# EasyEDAProPrj_Hackpad_numeric_keypad.net
KiCad netlist of a schematic drawn in EasyEDA Pro
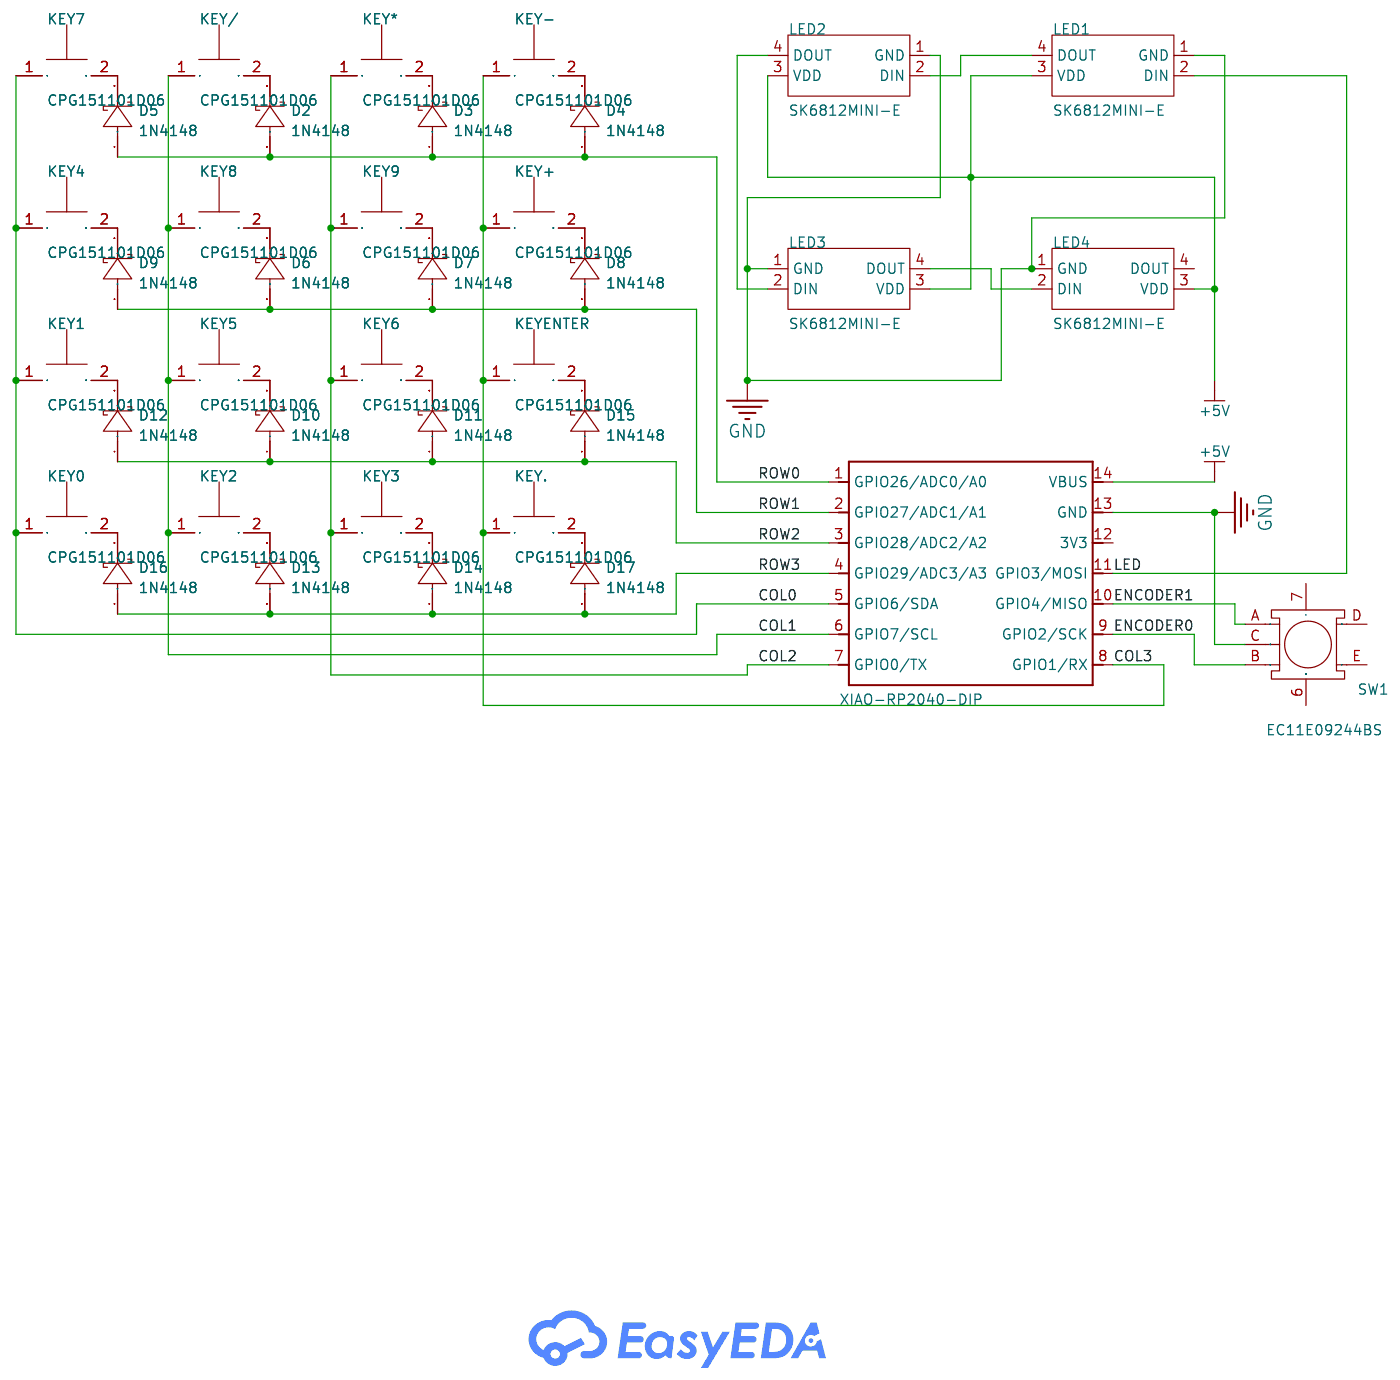
[diagram p0: schematic sheet]

(export (version "E")
  (design (tool "Eeschema 10.0.6"))
  (components
    (comp (ref "D2")
      (value "1N4148")
      (footprint "easyedapro:SOD-123_L2.7-W1.6-LS3.7-FD")
      (fields (field (name "Manufacturer") "LJ(朗捷)"))
      (libsource (lib "easyedapro") (part "1N4148W_C7420318"))
    )
    (comp (ref "D3")
      (value "1N4148")
      (footprint "easyedapro:SOD-123_L2.7-W1.6-LS3.7-FD")
      (fields (field (name "Manufacturer") "LJ(朗捷)"))
      (libsource (lib "easyedapro") (part "1N4148W_C7420318"))
    )
    (comp (ref "D4")
      (value "1N4148")
      (footprint "easyedapro:SOD-123_L2.7-W1.6-LS3.7-FD")
      (fields (field (name "Manufacturer") "LJ(朗捷)"))
      (libsource (lib "easyedapro") (part "1N4148W_C7420318"))
    )
    (comp (ref "D5")
      (value "1N4148")
      (footprint "easyedapro:SOD-123_L2.7-W1.6-LS3.7-FD")
      (fields (field (name "Manufacturer") "LJ(朗捷)"))
      (libsource (lib "easyedapro") (part "1N4148W_C7420318"))
    )
    (comp (ref "D6")
      (value "1N4148")
      (footprint "easyedapro:SOD-123_L2.7-W1.6-LS3.7-FD")
      (fields (field (name "Manufacturer") "LJ(朗捷)"))
      (libsource (lib "easyedapro") (part "1N4148W_C7420318"))
    )
    (comp (ref "D7")
      (value "1N4148")
      (footprint "easyedapro:SOD-123_L2.7-W1.6-LS3.7-FD")
      (fields (field (name "Manufacturer") "LJ(朗捷)"))
      (libsource (lib "easyedapro") (part "1N4148W_C7420318"))
    )
    (comp (ref "D8")
      (value "1N4148")
      (footprint "easyedapro:SOD-123_L2.7-W1.6-LS3.7-FD")
      (fields (field (name "Manufacturer") "LJ(朗捷)"))
      (libsource (lib "easyedapro") (part "1N4148W_C7420318"))
    )
    (comp (ref "D9")
      (value "1N4148")
      (footprint "easyedapro:SOD-123_L2.7-W1.6-LS3.7-FD")
      (fields (field (name "Manufacturer") "LJ(朗捷)"))
      (libsource (lib "easyedapro") (part "1N4148W_C7420318"))
    )
    (comp (ref "D10")
      (value "1N4148")
      (footprint "easyedapro:SOD-123_L2.7-W1.6-LS3.7-FD")
      (fields (field (name "Manufacturer") "LJ(朗捷)"))
      (libsource (lib "easyedapro") (part "1N4148W_C7420318"))
    )
    (comp (ref "D11")
      (value "1N4148")
      (footprint "easyedapro:SOD-123_L2.7-W1.6-LS3.7-FD")
      (fields (field (name "Manufacturer") "LJ(朗捷)"))
      (libsource (lib "easyedapro") (part "1N4148W_C7420318"))
    )
    (comp (ref "D12")
      (value "1N4148")
      (footprint "easyedapro:SOD-123_L2.7-W1.6-LS3.7-FD")
      (fields (field (name "Manufacturer") "LJ(朗捷)"))
      (libsource (lib "easyedapro") (part "1N4148W_C7420318"))
    )
    (comp (ref "D13")
      (value "1N4148")
      (footprint "easyedapro:SOD-123_L2.7-W1.6-LS3.7-FD")
      (fields (field (name "Manufacturer") "LJ(朗捷)"))
      (libsource (lib "easyedapro") (part "1N4148W_C7420318"))
    )
    (comp (ref "D14")
      (value "1N4148")
      (footprint "easyedapro:SOD-123_L2.7-W1.6-LS3.7-FD")
      (fields (field (name "Manufacturer") "LJ(朗捷)"))
      (libsource (lib "easyedapro") (part "1N4148W_C7420318"))
    )
    (comp (ref "D15")
      (value "1N4148")
      (footprint "easyedapro:SOD-123_L2.7-W1.6-LS3.7-FD")
      (fields (field (name "Manufacturer") "LJ(朗捷)"))
      (libsource (lib "easyedapro") (part "1N4148W_C7420318"))
    )
    (comp (ref "D16")
      (value "1N4148")
      (footprint "easyedapro:SOD-123_L2.7-W1.6-LS3.7-FD")
      (fields (field (name "Manufacturer") "LJ(朗捷)"))
      (libsource (lib "easyedapro") (part "1N4148W_C7420318"))
    )
    (comp (ref "D17")
      (value "1N4148")
      (footprint "easyedapro:SOD-123_L2.7-W1.6-LS3.7-FD")
      (fields (field (name "Manufacturer") "LJ(朗捷)"))
      (libsource (lib "easyedapro") (part "1N4148W_C7420318"))
    )
    (comp (ref "KEY*")
      (value "CPG151101D06")
      (footprint "easyedapro:KEY-TH_CPG151101D06")
      (fields (field (name "Manufacturer") "HanElectricity(瀚源)"))
      (libsource (lib "easyedapro") (part "CPG151101D06"))
    )
    (comp (ref "KEY+")
      (value "CPG151101D06")
      (footprint "easyedapro:KEY-TH_CPG151101D06")
      (fields (field (name "Manufacturer") "HanElectricity(瀚源)"))
      (libsource (lib "easyedapro") (part "CPG151101D06"))
    )
    (comp (ref "KEY-")
      (value "CPG151101D06")
      (footprint "easyedapro:KEY-TH_CPG151101D06")
      (fields (field (name "Manufacturer") "HanElectricity(瀚源)"))
      (libsource (lib "easyedapro") (part "CPG151101D06"))
    )
    (comp (ref "KEY.")
      (value "CPG151101D06")
      (footprint "easyedapro:KEY-TH_CPG151101D06")
      (fields (field (name "Manufacturer") "HanElectricity(瀚源)"))
      (libsource (lib "easyedapro") (part "CPG151101D06"))
    )
    (comp (ref "KEY/")
      (value "CPG151101D06")
      (footprint "easyedapro:KEY-TH_CPG151101D06")
      (fields (field (name "Manufacturer") "HanElectricity(瀚源)"))
      (libsource (lib "easyedapro") (part "CPG151101D06"))
    )
    (comp (ref "KEY0")
      (value "CPG151101D06")
      (footprint "easyedapro:KEY-TH_CPG151101D06")
      (fields (field (name "Manufacturer") "HanElectricity(瀚源)"))
      (libsource (lib "easyedapro") (part "CPG151101D06"))
    )
    (comp (ref "KEY1")
      (value "CPG151101D06")
      (footprint "easyedapro:KEY-TH_CPG151101D06")
      (fields (field (name "Manufacturer") "HanElectricity(瀚源)"))
      (libsource (lib "easyedapro") (part "CPG151101D06"))
    )
    (comp (ref "KEY2")
      (value "CPG151101D06")
      (footprint "easyedapro:KEY-TH_CPG151101D06")
      (fields (field (name "Manufacturer") "HanElectricity(瀚源)"))
      (libsource (lib "easyedapro") (part "CPG151101D06"))
    )
    (comp (ref "KEY3")
      (value "CPG151101D06")
      (footprint "easyedapro:KEY-TH_CPG151101D06")
      (fields (field (name "Manufacturer") "HanElectricity(瀚源)"))
      (libsource (lib "easyedapro") (part "CPG151101D06"))
    )
    (comp (ref "KEY4")
      (value "CPG151101D06")
      (footprint "easyedapro:KEY-TH_CPG151101D06")
      (fields (field (name "Manufacturer") "HanElectricity(瀚源)"))
      (libsource (lib "easyedapro") (part "CPG151101D06"))
    )
    (comp (ref "KEY5")
      (value "CPG151101D06")
      (footprint "easyedapro:KEY-TH_CPG151101D06")
      (fields (field (name "Manufacturer") "HanElectricity(瀚源)"))
      (libsource (lib "easyedapro") (part "CPG151101D06"))
    )
    (comp (ref "KEY6")
      (value "CPG151101D06")
      (footprint "easyedapro:KEY-TH_CPG151101D06")
      (fields (field (name "Manufacturer") "HanElectricity(瀚源)"))
      (libsource (lib "easyedapro") (part "CPG151101D06"))
    )
    (comp (ref "KEY7")
      (value "CPG151101D06")
      (footprint "easyedapro:KEY-TH_CPG151101D06")
      (fields (field (name "Manufacturer") "HanElectricity(瀚源)"))
      (libsource (lib "easyedapro") (part "CPG151101D06"))
    )
    (comp (ref "KEY8")
      (value "CPG151101D06")
      (footprint "easyedapro:KEY-TH_CPG151101D06")
      (fields (field (name "Manufacturer") "HanElectricity(瀚源)"))
      (libsource (lib "easyedapro") (part "CPG151101D06"))
    )
    (comp (ref "KEY9")
      (value "CPG151101D06")
      (footprint "easyedapro:KEY-TH_CPG151101D06")
      (fields (field (name "Manufacturer") "HanElectricity(瀚源)"))
      (libsource (lib "easyedapro") (part "CPG151101D06"))
    )
    (comp (ref "KEYENTER")
      (value "CPG151101D06")
      (footprint "easyedapro:KEY-TH_CPG151101D06")
      (fields (field (name "Manufacturer") "HanElectricity(瀚源)"))
      (libsource (lib "easyedapro") (part "CPG151101D06"))
    )
    (comp (ref "LED1")
      (value "SK6812MINI-E")
      (footprint "easyedapro:LED-SMD_4P-L3.2-W2.8-LS5.9_SK6812MINI-E")
      (fields (field (name "Manufacturer") "欧思科光电"))
      (libsource (lib "easyedapro") (part "SK6812_C5378720"))
    )
    (comp (ref "LED2")
      (value "SK6812MINI-E")
      (footprint "easyedapro:LED-SMD_4P-L3.2-W2.8-LS5.9_SK6812MINI-E")
      (fields (field (name "Manufacturer") "欧思科光电"))
      (libsource (lib "easyedapro") (part "SK6812_C5378720"))
    )
    (comp (ref "LED3")
      (value "SK6812MINI-E")
      (footprint "easyedapro:LED-SMD_4P-L3.2-W2.8-LS5.9_SK6812MINI-E")
      (fields (field (name "Manufacturer") "欧思科光电"))
      (libsource (lib "easyedapro") (part "SK6812_C5378720"))
    )
    (comp (ref "LED4")
      (value "SK6812MINI-E")
      (footprint "easyedapro:LED-SMD_4P-L3.2-W2.8-LS5.9_SK6812MINI-E")
      (fields (field (name "Manufacturer") "欧思科光电"))
      (libsource (lib "easyedapro") (part "SK6812_C5378720"))
    )
    (comp (ref "SW1")
      (value "EC11E09244BS")
      (footprint "easyedapro:SW-TH_EC11XXXXXXXX")
      (fields (field (name "Manufacturer") "ALPSALPINE(阿尔卑斯阿尔派)"))
      (libsource (lib "easyedapro") (part "EC11E09244BS"))
    )
    (comp (ref "U1") (value "XIAO-RP2040-DIP") (libsource (lib "easyedapro") (part "XIAO-RP2040-DIP")))
  )
  (nets
    (net (code "1") (name "+5V") (class "Default")
      (node (ref "LED1") (pin "3") (pinfunction "VDD_3") (pintype "unspecified"))
      (node (ref "LED2") (pin "3") (pinfunction "VDD_3") (pintype "unspecified"))
      (node (ref "LED3") (pin "3") (pinfunction "VDD_3") (pintype "unspecified"))
      (node (ref "LED4") (pin "3") (pinfunction "VDD_3") (pintype "unspecified"))
      (node (ref "U1") (pin "14") (pinfunction "VBUS_14") (pintype "unspecified"))
    )
    (net (code "2") (name "/COL0") (class "Default")
      (node (ref "KEY0") (pin "1") (pinfunction "1_1") (pintype "unspecified"))
      (node (ref "KEY1") (pin "1") (pinfunction "1_1") (pintype "unspecified"))
      (node (ref "KEY4") (pin "1") (pinfunction "1_1") (pintype "unspecified"))
      (node (ref "KEY7") (pin "1") (pinfunction "1_1") (pintype "unspecified"))
      (node (ref "U1") (pin "5") (pinfunction "GPIO6/SDA_5") (pintype "unspecified"))
    )
    (net (code "3") (name "/COL1") (class "Default")
      (node (ref "KEY/") (pin "1") (pinfunction "1_1") (pintype "unspecified"))
      (node (ref "KEY2") (pin "1") (pinfunction "1_1") (pintype "unspecified"))
      (node (ref "KEY5") (pin "1") (pinfunction "1_1") (pintype "unspecified"))
      (node (ref "KEY8") (pin "1") (pinfunction "1_1") (pintype "unspecified"))
      (node (ref "U1") (pin "6") (pinfunction "GPIO7/SCL_6") (pintype "unspecified"))
    )
    (net (code "4") (name "/COL2") (class "Default")
      (node (ref "KEY*") (pin "1") (pinfunction "1_1") (pintype "unspecified"))
      (node (ref "KEY3") (pin "1") (pinfunction "1_1") (pintype "unspecified"))
      (node (ref "KEY6") (pin "1") (pinfunction "1_1") (pintype "unspecified"))
      (node (ref "KEY9") (pin "1") (pinfunction "1_1") (pintype "unspecified"))
      (node (ref "U1") (pin "7") (pinfunction "GPIO0/TX_7") (pintype "unspecified"))
    )
    (net (code "5") (name "/COL3") (class "Default")
      (node (ref "KEY+") (pin "1") (pinfunction "1_1") (pintype "unspecified"))
      (node (ref "KEY-") (pin "1") (pinfunction "1_1") (pintype "unspecified"))
      (node (ref "KEY.") (pin "1") (pinfunction "1_1") (pintype "unspecified"))
      (node (ref "KEYENTER") (pin "1") (pinfunction "1_1") (pintype "unspecified"))
      (node (ref "U1") (pin "8") (pinfunction "GPIO1/RX_8") (pintype "unspecified"))
    )
    (net (code "6") (name "/ENCODER0") (class "Default")
      (node (ref "SW1") (pin "B") (pinfunction "B_B") (pintype "unspecified"))
      (node (ref "U1") (pin "9") (pinfunction "GPIO2/SCK_9") (pintype "unspecified"))
    )
    (net (code "7") (name "/ENCODER1") (class "Default")
      (node (ref "SW1") (pin "A") (pinfunction "A_A") (pintype "unspecified"))
      (node (ref "U1") (pin "10") (pinfunction "GPIO4/MISO_10") (pintype "unspecified"))
    )
    (net (code "8") (name "/LED") (class "Default")
      (node (ref "LED1") (pin "2") (pinfunction "DIN_2") (pintype "unspecified"))
      (node (ref "U1") (pin "11") (pinfunction "GPIO3/MOSI_11") (pintype "unspecified"))
    )
    (net (code "9") (name "/ROW0") (class "Default")
      (node (ref "D2") (pin "1") (pinfunction "A_1") (pintype "unspecified"))
      (node (ref "D3") (pin "1") (pinfunction "A_1") (pintype "unspecified"))
      (node (ref "D4") (pin "1") (pinfunction "A_1") (pintype "unspecified"))
      (node (ref "D5") (pin "1") (pinfunction "A_1") (pintype "unspecified"))
      (node (ref "U1") (pin "1") (pinfunction "GPIO26/ADC0/A0_1") (pintype "unspecified"))
    )
    (net (code "10") (name "/ROW1") (class "Default")
      (node (ref "D6") (pin "1") (pinfunction "A_1") (pintype "unspecified"))
      (node (ref "D7") (pin "1") (pinfunction "A_1") (pintype "unspecified"))
      (node (ref "D8") (pin "1") (pinfunction "A_1") (pintype "unspecified"))
      (node (ref "D9") (pin "1") (pinfunction "A_1") (pintype "unspecified"))
      (node (ref "U1") (pin "2") (pinfunction "GPIO27/ADC1/A1_2") (pintype "unspecified"))
    )
    (net (code "11") (name "/ROW2") (class "Default")
      (node (ref "D10") (pin "1") (pinfunction "A_1") (pintype "unspecified"))
      (node (ref "D11") (pin "1") (pinfunction "A_1") (pintype "unspecified"))
      (node (ref "D12") (pin "1") (pinfunction "A_1") (pintype "unspecified"))
      (node (ref "D15") (pin "1") (pinfunction "A_1") (pintype "unspecified"))
      (node (ref "U1") (pin "3") (pinfunction "GPIO28/ADC2/A2_3") (pintype "unspecified"))
    )
    (net (code "12") (name "/ROW3") (class "Default")
      (node (ref "D13") (pin "1") (pinfunction "A_1") (pintype "unspecified"))
      (node (ref "D14") (pin "1") (pinfunction "A_1") (pintype "unspecified"))
      (node (ref "D16") (pin "1") (pinfunction "A_1") (pintype "unspecified"))
      (node (ref "D17") (pin "1") (pinfunction "A_1") (pintype "unspecified"))
      (node (ref "U1") (pin "4") (pinfunction "GPIO29/ADC3/A3_4") (pintype "unspecified"))
    )
    (net (code "13") (name "GND") (class "Default")
      (node (ref "LED1") (pin "1") (pinfunction "GND_1") (pintype "unspecified"))
      (node (ref "LED2") (pin "1") (pinfunction "GND_1") (pintype "unspecified"))
      (node (ref "LED3") (pin "1") (pinfunction "GND_1") (pintype "unspecified"))
      (node (ref "LED4") (pin "1") (pinfunction "GND_1") (pintype "unspecified"))
      (node (ref "SW1") (pin "C") (pinfunction "C_C") (pintype "unspecified"))
      (node (ref "U1") (pin "13") (pinfunction "GND_13") (pintype "unspecified"))
    )
    (net (code "14") (name "Net-(D2-K)") (class "Default")
      (node (ref "D2") (pin "2") (pinfunction "K_2") (pintype "unspecified"))
      (node (ref "KEY/") (pin "2") (pinfunction "2_2") (pintype "unspecified"))
    )
    (net (code "15") (name "Net-(D3-K)") (class "Default")
      (node (ref "D3") (pin "2") (pinfunction "K_2") (pintype "unspecified"))
      (node (ref "KEY*") (pin "2") (pinfunction "2_2") (pintype "unspecified"))
    )
    (net (code "16") (name "Net-(D4-K)") (class "Default")
      (node (ref "D4") (pin "2") (pinfunction "K_2") (pintype "unspecified"))
      (node (ref "KEY-") (pin "2") (pinfunction "2_2") (pintype "unspecified"))
    )
    (net (code "17") (name "Net-(D5-K)") (class "Default")
      (node (ref "D5") (pin "2") (pinfunction "K_2") (pintype "unspecified"))
      (node (ref "KEY7") (pin "2") (pinfunction "2_2") (pintype "unspecified"))
    )
    (net (code "18") (name "Net-(D6-K)") (class "Default")
      (node (ref "D6") (pin "2") (pinfunction "K_2") (pintype "unspecified"))
      (node (ref "KEY8") (pin "2") (pinfunction "2_2") (pintype "unspecified"))
    )
    (net (code "19") (name "Net-(D7-K)") (class "Default")
      (node (ref "D7") (pin "2") (pinfunction "K_2") (pintype "unspecified"))
      (node (ref "KEY9") (pin "2") (pinfunction "2_2") (pintype "unspecified"))
    )
    (net (code "20") (name "Net-(D8-K)") (class "Default")
      (node (ref "D8") (pin "2") (pinfunction "K_2") (pintype "unspecified"))
      (node (ref "KEY+") (pin "2") (pinfunction "2_2") (pintype "unspecified"))
    )
    (net (code "21") (name "Net-(D9-K)") (class "Default")
      (node (ref "D9") (pin "2") (pinfunction "K_2") (pintype "unspecified"))
      (node (ref "KEY4") (pin "2") (pinfunction "2_2") (pintype "unspecified"))
    )
    (net (code "22") (name "Net-(D10-K)") (class "Default")
      (node (ref "D10") (pin "2") (pinfunction "K_2") (pintype "unspecified"))
      (node (ref "KEY5") (pin "2") (pinfunction "2_2") (pintype "unspecified"))
    )
    (net (code "23") (name "Net-(D11-K)") (class "Default")
      (node (ref "D11") (pin "2") (pinfunction "K_2") (pintype "unspecified"))
      (node (ref "KEY6") (pin "2") (pinfunction "2_2") (pintype "unspecified"))
    )
    (net (code "24") (name "Net-(D12-K)") (class "Default")
      (node (ref "D12") (pin "2") (pinfunction "K_2") (pintype "unspecified"))
      (node (ref "KEY1") (pin "2") (pinfunction "2_2") (pintype "unspecified"))
    )
    (net (code "25") (name "Net-(D13-K)") (class "Default")
      (node (ref "D13") (pin "2") (pinfunction "K_2") (pintype "unspecified"))
      (node (ref "KEY2") (pin "2") (pinfunction "2_2") (pintype "unspecified"))
    )
    (net (code "26") (name "Net-(D14-K)") (class "Default")
      (node (ref "D14") (pin "2") (pinfunction "K_2") (pintype "unspecified"))
      (node (ref "KEY3") (pin "2") (pinfunction "2_2") (pintype "unspecified"))
    )
    (net (code "27") (name "Net-(D15-K)") (class "Default")
      (node (ref "D15") (pin "2") (pinfunction "K_2") (pintype "unspecified"))
      (node (ref "KEYENTER") (pin "2") (pinfunction "2_2") (pintype "unspecified"))
    )
    (net (code "28") (name "Net-(D16-K)") (class "Default")
      (node (ref "D16") (pin "2") (pinfunction "K_2") (pintype "unspecified"))
      (node (ref "KEY0") (pin "2") (pinfunction "2_2") (pintype "unspecified"))
    )
    (net (code "29") (name "Net-(D17-K)") (class "Default")
      (node (ref "D17") (pin "2") (pinfunction "K_2") (pintype "unspecified"))
      (node (ref "KEY.") (pin "2") (pinfunction "2_2") (pintype "unspecified"))
    )
    (net (code "30") (name "Net-(LED1-DOUT)") (class "Default")
      (node (ref "LED1") (pin "4") (pinfunction "DOUT_4") (pintype "unspecified"))
      (node (ref "LED2") (pin "2") (pinfunction "DIN_2") (pintype "unspecified"))
    )
    (net (code "31") (name "Net-(LED2-DOUT)") (class "Default")
      (node (ref "LED2") (pin "4") (pinfunction "DOUT_4") (pintype "unspecified"))
      (node (ref "LED3") (pin "2") (pinfunction "DIN_2") (pintype "unspecified"))
    )
    (net (code "32") (name "Net-(LED3-DOUT)") (class "Default")
      (node (ref "LED3") (pin "4") (pinfunction "DOUT_4") (pintype "unspecified"))
      (node (ref "LED4") (pin "2") (pinfunction "DIN_2") (pintype "unspecified"))
    )
    (net (code "33") (name "unconnected-(LED4-DOUT-Pad4)") (class "Default")
      (node (ref "LED4") (pin "4") (pinfunction "DOUT_4") (pintype "unspecified"))
    )
    (net (code "34") (name "unconnected-(SW1-Pad6)") (class "Default")
      (node (ref "SW1") (pin "6") (pinfunction "6_6") (pintype "unspecified"))
    )
    (net (code "35") (name "unconnected-(SW1-Pad7)") (class "Default")
      (node (ref "SW1") (pin "7") (pinfunction "7_7") (pintype "unspecified"))
    )
    (net (code "36") (name "unconnected-(SW1-PadD)") (class "Default")
      (node (ref "SW1") (pin "D") (pinfunction "D_D") (pintype "unspecified"))
    )
    (net (code "37") (name "unconnected-(SW1-PadE)") (class "Default")
      (node (ref "SW1") (pin "E") (pinfunction "E_E") (pintype "unspecified"))
    )
    (net (code "38") (name "unconnected-(U1-3V3-Pad12)") (class "Default")
      (node (ref "U1") (pin "12") (pinfunction "3V3_12") (pintype "unspecified"))
    )
  )
)
